# UART_CHANGER_INDICATION.net
KiCad netlist of a schematic drawn in Altium Designer
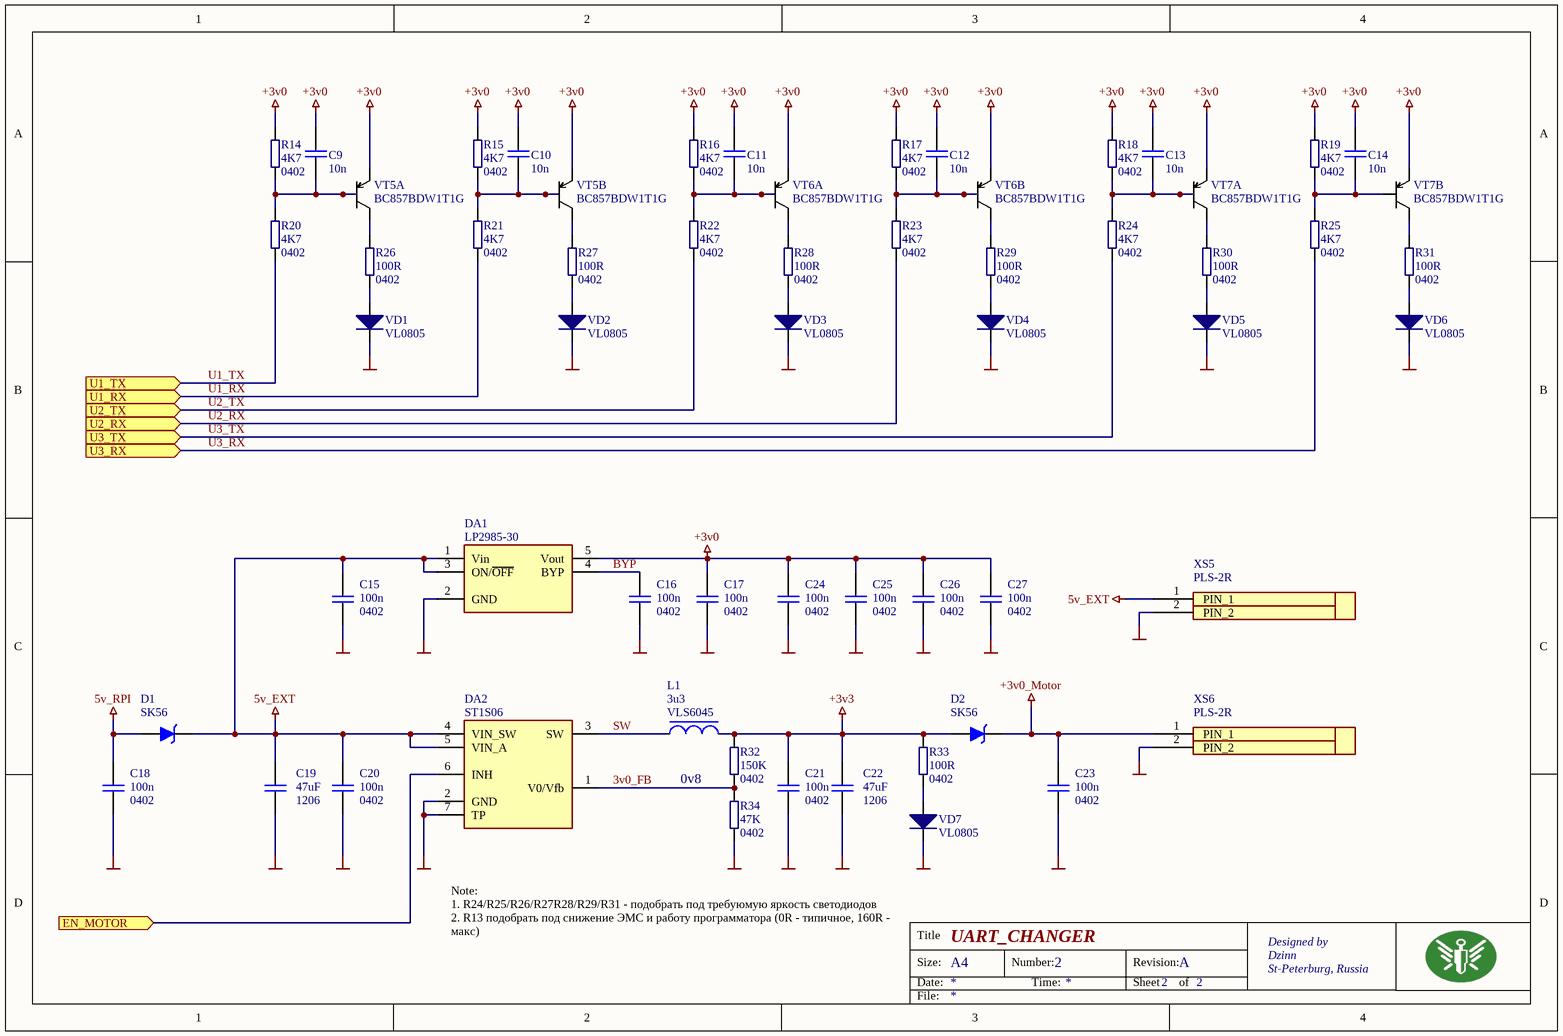
[diagram p0: UART_CHANGER_INDICATION.SchDoc]

(export (version "E")
  (design (tool "Eeschema 10.0.6"))
  (components
    (comp (ref "C9")
      (value "10n")
      (footprint "0402")
      (description "CAP 0402 100n")
      (fields
        (field (name "PART NUMBER") "C000001")
        (field (name "MANUFACTURER") "Murata")
        (field (name "CHECK FOOTPRINT") "A")
        (field (name "CHECK SYMBOL") "A")
      )
      (libsource (lib "Dzinn_lib") (part "CAP_NP"))
    )
    (comp (ref "C10")
      (value "10n")
      (footprint "0402")
      (description "CAP 0402 100n")
      (fields
        (field (name "PART NUMBER") "C000001")
        (field (name "MANUFACTURER") "Murata")
        (field (name "CHECK FOOTPRINT") "A")
        (field (name "CHECK SYMBOL") "A")
      )
      (libsource (lib "Dzinn_lib") (part "CAP_NP"))
    )
    (comp (ref "C11")
      (value "10n")
      (footprint "0402")
      (description "CAP 0402 100n")
      (fields
        (field (name "PART NUMBER") "C000001")
        (field (name "MANUFACTURER") "Murata")
        (field (name "CHECK FOOTPRINT") "A")
        (field (name "CHECK SYMBOL") "A")
      )
      (libsource (lib "Dzinn_lib") (part "CAP_NP"))
    )
    (comp (ref "C12")
      (value "10n")
      (footprint "0402")
      (description "CAP 0402 100n")
      (fields
        (field (name "PART NUMBER") "C000001")
        (field (name "MANUFACTURER") "Murata")
        (field (name "CHECK FOOTPRINT") "A")
        (field (name "CHECK SYMBOL") "A")
      )
      (libsource (lib "Dzinn_lib") (part "CAP_NP"))
    )
    (comp (ref "C13")
      (value "10n")
      (footprint "0402")
      (description "CAP 0402 100n")
      (fields
        (field (name "PART NUMBER") "C000001")
        (field (name "MANUFACTURER") "Murata")
        (field (name "CHECK FOOTPRINT") "A")
        (field (name "CHECK SYMBOL") "A")
      )
      (libsource (lib "Dzinn_lib") (part "CAP_NP"))
    )
    (comp (ref "C14")
      (value "10n")
      (footprint "0402")
      (description "CAP 0402 100n")
      (fields
        (field (name "PART NUMBER") "C000001")
        (field (name "MANUFACTURER") "Murata")
        (field (name "CHECK FOOTPRINT") "A")
        (field (name "CHECK SYMBOL") "A")
      )
      (libsource (lib "Dzinn_lib") (part "CAP_NP"))
    )
    (comp (ref "C15")
      (value "100n")
      (footprint "0402")
      (description "CAP 0402 100n")
      (fields
        (field (name "PART NUMBER") "C000001")
        (field (name "MANUFACTURER") "Murata")
        (field (name "PACKAGE") "0402")
        (field (name "CHECK FOOTPRINT") "A")
        (field (name "CHECK SYMBOL") "A")
      )
      (libsource (lib "Dzinn_lib") (part "CAP_NP"))
    )
    (comp (ref "C16")
      (value "100n")
      (footprint "0402")
      (description "CAP 0402 100n")
      (fields
        (field (name "PART NUMBER") "C000001")
        (field (name "MANUFACTURER") "Murata")
        (field (name "PACKAGE") "0402")
        (field (name "CHECK FOOTPRINT") "A")
        (field (name "CHECK SYMBOL") "A")
      )
      (libsource (lib "Dzinn_lib") (part "CAP_NP"))
    )
    (comp (ref "C17")
      (value "100n")
      (footprint "0402")
      (description "CAP 0402 100n")
      (fields
        (field (name "PART NUMBER") "C000001")
        (field (name "MANUFACTURER") "Murata")
        (field (name "PACKAGE") "0402")
        (field (name "CHECK FOOTPRINT") "A")
        (field (name "CHECK SYMBOL") "A")
      )
      (libsource (lib "Dzinn_lib") (part "CAP_NP"))
    )
    (comp (ref "C18")
      (value "100n")
      (footprint "0402")
      (description "CAP 0402 100n")
      (fields
        (field (name "PART NUMBER") "C000001")
        (field (name "MANUFACTURER") "Murata")
        (field (name "PACKAGE") "0402")
        (field (name "CHECK FOOTPRINT") "A")
        (field (name "CHECK SYMBOL") "A")
      )
      (libsource (lib "Dzinn_lib") (part "CAP_NP"))
    )
    (comp (ref "C19")
      (value "47uF")
      (footprint "1206")
      (description "CAP 1206 47uF 10V")
      (fields
        (field (name "PACKAGE") "1206")
        (field (name "PART NUMBER") "C000003")
        (field (name "MANUFACTURER") "Murata")
        (field (name "CHECK FOOTPRINT") "A")
        (field (name "CHECK SYMBOL") "A")
      )
      (libsource (lib "") (part "CAP_NP_1"))
    )
    (comp (ref "C20")
      (value "100n")
      (footprint "0402")
      (description "CAP 0402 100n")
      (fields
        (field (name "PART NUMBER") "C000001")
        (field (name "MANUFACTURER") "Murata")
        (field (name "PACKAGE") "0402")
        (field (name "CHECK FOOTPRINT") "A")
        (field (name "CHECK SYMBOL") "A")
      )
      (libsource (lib "Dzinn_lib") (part "CAP_NP"))
    )
    (comp (ref "C21")
      (value "100n")
      (footprint "0402")
      (description "CAP 0402 100n")
      (fields
        (field (name "PART NUMBER") "C000001")
        (field (name "MANUFACTURER") "Murata")
        (field (name "PACKAGE") "0402")
        (field (name "CHECK FOOTPRINT") "A")
        (field (name "CHECK SYMBOL") "A")
      )
      (libsource (lib "Dzinn_lib") (part "CAP_NP"))
    )
    (comp (ref "C22")
      (value "47uF")
      (footprint "1206")
      (description "CAP 1206 47uF 10V")
      (fields
        (field (name "PACKAGE") "1206")
        (field (name "PART NUMBER") "C000003")
        (field (name "MANUFACTURER") "Murata")
        (field (name "CHECK FOOTPRINT") "A")
        (field (name "CHECK SYMBOL") "A")
      )
      (libsource (lib "") (part "CAP_NP_1"))
    )
    (comp (ref "C23")
      (value "100n")
      (footprint "0402")
      (description "CAP 0402 100n")
      (fields
        (field (name "PART NUMBER") "C000001")
        (field (name "MANUFACTURER") "Murata")
        (field (name "PACKAGE") "0402")
        (field (name "CHECK FOOTPRINT") "A")
        (field (name "CHECK SYMBOL") "A")
      )
      (libsource (lib "Dzinn_lib") (part "CAP_NP"))
    )
    (comp (ref "C24")
      (value "100n")
      (footprint "0402")
      (description "CAP 0402 100n")
      (fields
        (field (name "PART NUMBER") "C000001")
        (field (name "MANUFACTURER") "Murata")
        (field (name "PACKAGE") "0402")
        (field (name "CHECK FOOTPRINT") "A")
        (field (name "CHECK SYMBOL") "A")
      )
      (libsource (lib "Dzinn_lib") (part "CAP_NP"))
    )
    (comp (ref "C25")
      (value "100n")
      (footprint "0402")
      (description "CAP 0402 100n")
      (fields
        (field (name "PART NUMBER") "C000001")
        (field (name "MANUFACTURER") "Murata")
        (field (name "PACKAGE") "0402")
        (field (name "CHECK FOOTPRINT") "A")
        (field (name "CHECK SYMBOL") "A")
      )
      (libsource (lib "Dzinn_lib") (part "CAP_NP"))
    )
    (comp (ref "C26")
      (value "100n")
      (footprint "0402")
      (description "CAP 0402 100n")
      (fields
        (field (name "PART NUMBER") "C000001")
        (field (name "MANUFACTURER") "Murata")
        (field (name "PACKAGE") "0402")
        (field (name "CHECK FOOTPRINT") "A")
        (field (name "CHECK SYMBOL") "A")
      )
      (libsource (lib "Dzinn_lib") (part "CAP_NP"))
    )
    (comp (ref "C27")
      (value "100n")
      (footprint "0402")
      (description "CAP 0402 100n")
      (fields
        (field (name "PART NUMBER") "C000001")
        (field (name "MANUFACTURER") "Murata")
        (field (name "PACKAGE") "0402")
        (field (name "CHECK FOOTPRINT") "A")
        (field (name "CHECK SYMBOL") "A")
      )
      (libsource (lib "Dzinn_lib") (part "CAP_NP"))
    )
    (comp (ref "D1")
      (value "SK56")
      (footprint "SMB")
      (description "60V 5A Schottky Diode")
      (fields
        (field (name "PART NUMBER") "VD00002")
        (field (name "MANUFACTURER") "SMC")
        (field (name "CHECK FOOTPRINT") "A")
        (field (name "CHECK SYMBOL") "A")
      )
      (libsource (lib "Dzinn_lib") (part "DIODE Schottky"))
    )
    (comp (ref "D2")
      (value "SK56")
      (footprint "SMB")
      (description "60V 5A Schottky Diode")
      (fields
        (field (name "PART NUMBER") "VD00002")
        (field (name "MANUFACTURER") "SMC")
        (field (name "CHECK FOOTPRINT") "A")
        (field (name "CHECK SYMBOL") "A")
      )
      (libsource (lib "Dzinn_lib") (part "DIODE Schottky"))
    )
    (comp (ref "DA1")
      (value "LP2985-30")
      (footprint "SOT-23-5")
      (description "150-mA Low-noise Low-dropout Regulator With Shutdown")
      (fields
        (field (name "PART NUMBER") "U00007")
        (field (name "MANUFACTURER") "TI")
        (field (name "CHECK FOOTPRINT") "B")
        (field (name "CHECK SYMBOL") "B")
      )
      (libsource (lib "Dzinn_lib") (part "LP2985-XX"))
    )
    (comp (ref "DA2")
      (value "ST1S06")
      (footprint "DFN-6TP")
      (fields
        (field (name "PART NUMBER") "U00027")
        (field (name "MANUFACTURER") "ST")
        (field (name "CHECK FOOTPRINT") "A")
        (field (name "CHECK SYMBOL") "A")
      )
      (libsource (lib "Dzinn_lib") (part "ST1S06"))
    )
    (comp (ref "L1")
      (value "3u3")
      (footprint "VLS6045")
      (description "3u3H smd power induction")
      (fields
        (field (name "PART NUMBER") "IND000010")
        (field (name "MANUFACTURER") "TDK")
        (field (name "PACKAGE") "VLS6045")
        (field (name "CHECK FOOTPRINT") "A")
        (field (name "CHECK SYMBOL") "A")
      )
      (libsource (lib "Dzinn_lib") (part "IND"))
    )
    (comp (ref "R14")
      (value "4K7")
      (footprint "0402")
      (description "RES SMD")
      (fields
        (field (name "PART NUMBER") "R000090")
        (field (name "MANUFACTURER") "Rohm Semiconductor")
        (field (name "PACKAGE") "0402")
        (field (name "CHECK FOOTPRINT") "A")
        (field (name "CHECK SYMBOL") "A")
      )
      (libsource (lib "Dzinn_lib") (part "RES"))
    )
    (comp (ref "R15")
      (value "4K7")
      (footprint "0402")
      (description "RES SMD")
      (fields
        (field (name "PART NUMBER") "R000090")
        (field (name "MANUFACTURER") "Rohm Semiconductor")
        (field (name "PACKAGE") "0402")
        (field (name "CHECK FOOTPRINT") "A")
        (field (name "CHECK SYMBOL") "A")
      )
      (libsource (lib "Dzinn_lib") (part "RES"))
    )
    (comp (ref "R16")
      (value "4K7")
      (footprint "0402")
      (description "RES SMD")
      (fields
        (field (name "PART NUMBER") "R000090")
        (field (name "MANUFACTURER") "Rohm Semiconductor")
        (field (name "PACKAGE") "0402")
        (field (name "CHECK FOOTPRINT") "A")
        (field (name "CHECK SYMBOL") "A")
      )
      (libsource (lib "Dzinn_lib") (part "RES"))
    )
    (comp (ref "R17")
      (value "4K7")
      (footprint "0402")
      (description "RES SMD")
      (fields
        (field (name "PART NUMBER") "R000090")
        (field (name "MANUFACTURER") "Rohm Semiconductor")
        (field (name "PACKAGE") "0402")
        (field (name "CHECK FOOTPRINT") "A")
        (field (name "CHECK SYMBOL") "A")
      )
      (libsource (lib "Dzinn_lib") (part "RES"))
    )
    (comp (ref "R18")
      (value "4K7")
      (footprint "0402")
      (description "RES SMD")
      (fields
        (field (name "PART NUMBER") "R000090")
        (field (name "MANUFACTURER") "Rohm Semiconductor")
        (field (name "PACKAGE") "0402")
        (field (name "CHECK FOOTPRINT") "A")
        (field (name "CHECK SYMBOL") "A")
      )
      (libsource (lib "Dzinn_lib") (part "RES"))
    )
    (comp (ref "R19")
      (value "4K7")
      (footprint "0402")
      (description "RES SMD")
      (fields
        (field (name "PART NUMBER") "R000090")
        (field (name "MANUFACTURER") "Rohm Semiconductor")
        (field (name "PACKAGE") "0402")
        (field (name "CHECK FOOTPRINT") "A")
        (field (name "CHECK SYMBOL") "A")
      )
      (libsource (lib "Dzinn_lib") (part "RES"))
    )
    (comp (ref "R20")
      (value "4K7")
      (footprint "0402")
      (description "RES SMD")
      (fields
        (field (name "PART NUMBER") "R000090")
        (field (name "MANUFACTURER") "Rohm Semiconductor")
        (field (name "PACKAGE") "0402")
        (field (name "CHECK FOOTPRINT") "A")
        (field (name "CHECK SYMBOL") "A")
      )
      (libsource (lib "Dzinn_lib") (part "RES"))
    )
    (comp (ref "R21")
      (value "4K7")
      (footprint "0402")
      (description "RES SMD")
      (fields
        (field (name "PART NUMBER") "R000090")
        (field (name "MANUFACTURER") "Rohm Semiconductor")
        (field (name "PACKAGE") "0402")
        (field (name "CHECK FOOTPRINT") "A")
        (field (name "CHECK SYMBOL") "A")
      )
      (libsource (lib "Dzinn_lib") (part "RES"))
    )
    (comp (ref "R22")
      (value "4K7")
      (footprint "0402")
      (description "RES SMD")
      (fields
        (field (name "PART NUMBER") "R000090")
        (field (name "MANUFACTURER") "Rohm Semiconductor")
        (field (name "PACKAGE") "0402")
        (field (name "CHECK FOOTPRINT") "A")
        (field (name "CHECK SYMBOL") "A")
      )
      (libsource (lib "Dzinn_lib") (part "RES"))
    )
    (comp (ref "R23")
      (value "4K7")
      (footprint "0402")
      (description "RES SMD")
      (fields
        (field (name "PART NUMBER") "R000090")
        (field (name "MANUFACTURER") "Rohm Semiconductor")
        (field (name "PACKAGE") "0402")
        (field (name "CHECK FOOTPRINT") "A")
        (field (name "CHECK SYMBOL") "A")
      )
      (libsource (lib "Dzinn_lib") (part "RES"))
    )
    (comp (ref "R24")
      (value "4K7")
      (footprint "0402")
      (description "RES SMD")
      (fields
        (field (name "PART NUMBER") "R000090")
        (field (name "MANUFACTURER") "Rohm Semiconductor")
        (field (name "PACKAGE") "0402")
        (field (name "CHECK FOOTPRINT") "A")
        (field (name "CHECK SYMBOL") "A")
      )
      (libsource (lib "Dzinn_lib") (part "RES"))
    )
    (comp (ref "R25")
      (value "4K7")
      (footprint "0402")
      (description "RES SMD")
      (fields
        (field (name "PART NUMBER") "R000090")
        (field (name "MANUFACTURER") "Rohm Semiconductor")
        (field (name "PACKAGE") "0402")
        (field (name "CHECK FOOTPRINT") "A")
        (field (name "CHECK SYMBOL") "A")
      )
      (libsource (lib "Dzinn_lib") (part "RES"))
    )
    (comp (ref "R26")
      (value "100R")
      (footprint "0402")
      (description "RES SMD")
      (fields
        (field (name "PART NUMBER") "R000050")
        (field (name "MANUFACTURER") "Rohm Semiconductor")
        (field (name "PACKAGE") "0402")
        (field (name "CHECK FOOTPRINT") "A")
        (field (name "CHECK SYMBOL") "A")
      )
      (libsource (lib "Dzinn_lib") (part "RES"))
    )
    (comp (ref "R27")
      (value "100R")
      (footprint "0402")
      (description "RES SMD")
      (fields
        (field (name "PART NUMBER") "R000050")
        (field (name "MANUFACTURER") "Rohm Semiconductor")
        (field (name "PACKAGE") "0402")
        (field (name "CHECK FOOTPRINT") "A")
        (field (name "CHECK SYMBOL") "A")
      )
      (libsource (lib "Dzinn_lib") (part "RES"))
    )
    (comp (ref "R28")
      (value "100R")
      (footprint "0402")
      (description "RES SMD")
      (fields
        (field (name "PART NUMBER") "R000050")
        (field (name "MANUFACTURER") "Rohm Semiconductor")
        (field (name "PACKAGE") "0402")
        (field (name "CHECK FOOTPRINT") "A")
        (field (name "CHECK SYMBOL") "A")
      )
      (libsource (lib "Dzinn_lib") (part "RES"))
    )
    (comp (ref "R29")
      (value "100R")
      (footprint "0402")
      (description "RES SMD")
      (fields
        (field (name "PART NUMBER") "R000050")
        (field (name "MANUFACTURER") "Rohm Semiconductor")
        (field (name "PACKAGE") "0402")
        (field (name "CHECK FOOTPRINT") "A")
        (field (name "CHECK SYMBOL") "A")
      )
      (libsource (lib "Dzinn_lib") (part "RES"))
    )
    (comp (ref "R30")
      (value "100R")
      (footprint "0402")
      (description "RES SMD")
      (fields
        (field (name "PART NUMBER") "R000050")
        (field (name "MANUFACTURER") "Rohm Semiconductor")
        (field (name "PACKAGE") "0402")
        (field (name "CHECK FOOTPRINT") "A")
        (field (name "CHECK SYMBOL") "A")
      )
      (libsource (lib "Dzinn_lib") (part "RES"))
    )
    (comp (ref "R31")
      (value "100R")
      (footprint "0402")
      (description "RES SMD")
      (fields
        (field (name "PART NUMBER") "R000050")
        (field (name "MANUFACTURER") "Rohm Semiconductor")
        (field (name "PACKAGE") "0402")
        (field (name "CHECK FOOTPRINT") "A")
        (field (name "CHECK SYMBOL") "A")
      )
      (libsource (lib "Dzinn_lib") (part "RES"))
    )
    (comp (ref "R32")
      (value "150K")
      (footprint "0402")
      (description "RES SMD")
      (fields
        (field (name "PART NUMBER") "R000126")
        (field (name "MANUFACTURER") "Rohm Semiconductor")
        (field (name "PACKAGE") "0402")
        (field (name "CHECK FOOTPRINT") "A")
        (field (name "CHECK SYMBOL") "A")
      )
      (libsource (lib "Dzinn_lib") (part "RES"))
    )
    (comp (ref "R33")
      (value "100R")
      (footprint "0402")
      (description "RES SMD")
      (fields
        (field (name "PART NUMBER") "R000050")
        (field (name "MANUFACTURER") "Rohm Semiconductor")
        (field (name "PACKAGE") "0402")
        (field (name "CHECK FOOTPRINT") "A")
        (field (name "CHECK SYMBOL") "A")
      )
      (libsource (lib "Dzinn_lib") (part "RES"))
    )
    (comp (ref "R34")
      (value "47K")
      (footprint "0402")
      (description "RES SMD")
      (fields
        (field (name "PART NUMBER") "R000114")
        (field (name "MANUFACTURER") "Rohm Semiconductor")
        (field (name "PACKAGE") "0402")
        (field (name "CHECK FOOTPRINT") "A")
        (field (name "CHECK SYMBOL") "A")
      )
      (libsource (lib "Dzinn_lib") (part "RES"))
    )
    (comp (ref "VD1")
      (value "VL0805")
      (footprint "VL0805")
      (description "SMD LED 0805")
      (fields
        (field (name "PART NUMBER") "LED000002")
        (field (name "VOLTAGE") "3,2")
        (field (name "CHECK FOOTPRINT") "A")
        (field (name "CHECK SYMBOL") "A")
      )
      (libsource (lib "Dzinn_lib") (part "SMD_LED"))
    )
    (comp (ref "VD2")
      (value "VL0805")
      (footprint "VL0805")
      (description "SMD LED 0805")
      (fields
        (field (name "PART NUMBER") "LED000002")
        (field (name "VOLTAGE") "3,2")
        (field (name "CHECK FOOTPRINT") "A")
        (field (name "CHECK SYMBOL") "A")
      )
      (libsource (lib "Dzinn_lib") (part "SMD_LED"))
    )
    (comp (ref "VD3")
      (value "VL0805")
      (footprint "VL0805")
      (description "SMD LED 0805")
      (fields
        (field (name "PART NUMBER") "LED000002")
        (field (name "VOLTAGE") "3,2")
        (field (name "CHECK FOOTPRINT") "A")
        (field (name "CHECK SYMBOL") "A")
      )
      (libsource (lib "Dzinn_lib") (part "SMD_LED"))
    )
    (comp (ref "VD4")
      (value "VL0805")
      (footprint "VL0805")
      (description "SMD LED 0805")
      (fields
        (field (name "PART NUMBER") "LED000002")
        (field (name "VOLTAGE") "3,2")
        (field (name "CHECK FOOTPRINT") "A")
        (field (name "CHECK SYMBOL") "A")
      )
      (libsource (lib "Dzinn_lib") (part "SMD_LED"))
    )
    (comp (ref "VD5")
      (value "VL0805")
      (footprint "VL0805")
      (description "SMD LED 0805")
      (fields
        (field (name "PART NUMBER") "LED000002")
        (field (name "VOLTAGE") "3,2")
        (field (name "CHECK FOOTPRINT") "A")
        (field (name "CHECK SYMBOL") "A")
      )
      (libsource (lib "Dzinn_lib") (part "SMD_LED"))
    )
    (comp (ref "VD6")
      (value "VL0805")
      (footprint "VL0805")
      (description "SMD LED 0805")
      (fields
        (field (name "PART NUMBER") "LED000002")
        (field (name "VOLTAGE") "3,2")
        (field (name "CHECK FOOTPRINT") "A")
        (field (name "CHECK SYMBOL") "A")
      )
      (libsource (lib "Dzinn_lib") (part "SMD_LED"))
    )
    (comp (ref "VD7")
      (value "VL0805")
      (footprint "VL0805")
      (description "SMD LED 0805")
      (fields
        (field (name "PART NUMBER") "LED000002")
        (field (name "VOLTAGE") "3,2")
        (field (name "CHECK FOOTPRINT") "A")
        (field (name "CHECK SYMBOL") "A")
      )
      (libsource (lib "Dzinn_lib") (part "SMD_LED"))
    )
    (comp (ref "VT5")
      (value "BC857BDW1T1G")
      (footprint "SOT-363")
      (description "45V 100mA Dual PNP Transistor")
      (fields
        (field (name "PART NUMBER") "VT00009")
        (field (name "MANUFACTURER") "ON")
        (field (name "CHECK FOOTPRINT") "A")
        (field (name "CHECK SYMBOL") "A")
      )
      (libsource (lib "Dzinn_lib") (part "DUAL PNP"))
    )
    (comp (ref "VT6")
      (value "BC857BDW1T1G")
      (footprint "SOT-363")
      (description "45V 100mA Dual PNP Transistor")
      (fields
        (field (name "PART NUMBER") "VT00009")
        (field (name "MANUFACTURER") "ON")
        (field (name "CHECK FOOTPRINT") "A")
        (field (name "CHECK SYMBOL") "A")
      )
      (libsource (lib "Dzinn_lib") (part "DUAL PNP"))
    )
    (comp (ref "VT7")
      (value "BC857BDW1T1G")
      (footprint "SOT-363")
      (description "45V 100mA Dual PNP Transistor")
      (fields
        (field (name "PART NUMBER") "VT00009")
        (field (name "MANUFACTURER") "ON")
        (field (name "CHECK FOOTPRINT") "A")
        (field (name "CHECK SYMBOL") "A")
      )
      (libsource (lib "Dzinn_lib") (part "DUAL PNP"))
    )
    (comp (ref "XS5")
      (value "PLS-2R")
      (footprint "PLS-2R")
      (description "2 PIN PLS right angle")
      (fields
        (field (name "PART NUMBER") "XS00002")
        (field (name "MANUFACTURER") "TE")
        (field (name "CHECK FOOTPRINT") "A")
        (field (name "CHECK SYMBOL") "A")
      )
      (libsource (lib "Dzinn_lib") (part "2_PIN_CON"))
    )
    (comp (ref "XS6")
      (value "PLS-2R")
      (footprint "PLS-2R")
      (description "2 PIN PLS right angle")
      (fields
        (field (name "PART NUMBER") "XS00002")
        (field (name "MANUFACTURER") "TE")
        (field (name "CHECK FOOTPRINT") "A")
        (field (name "CHECK SYMBOL") "A")
      )
      (libsource (lib "Dzinn_lib") (part "2_PIN_CON"))
    )
  )
  (nets
    (net (code "1") (name "+3v0") (class "Default")
      (node (ref "C10") (pin "1") (pinfunction "1_1") (pintype "passive"))
      (node (ref "C11") (pin "1") (pinfunction "1_1") (pintype "passive"))
      (node (ref "C12") (pin "1") (pinfunction "1_1") (pintype "passive"))
      (node (ref "C13") (pin "1") (pinfunction "1_1") (pintype "passive"))
      (node (ref "C14") (pin "1") (pinfunction "1_1") (pintype "passive"))
      (node (ref "C17") (pin "1") (pinfunction "1_1") (pintype "passive"))
      (node (ref "C24") (pin "1") (pinfunction "1_1") (pintype "passive"))
      (node (ref "C25") (pin "1") (pinfunction "1_1") (pintype "passive"))
      (node (ref "C26") (pin "1") (pinfunction "1_1") (pintype "passive"))
      (node (ref "C27") (pin "1") (pinfunction "1_1") (pintype "passive"))
      (node (ref "C9") (pin "1") (pinfunction "1_1") (pintype "passive"))
      (node (ref "DA1") (pin "5") (pinfunction "Vout_5") (pintype "passive"))
      (node (ref "R14") (pin "2") (pinfunction "2_2") (pintype "passive"))
      (node (ref "R15") (pin "2") (pinfunction "2_2") (pintype "passive"))
      (node (ref "R16") (pin "2") (pinfunction "2_2") (pintype "passive"))
      (node (ref "R17") (pin "2") (pinfunction "2_2") (pintype "passive"))
      (node (ref "R18") (pin "2") (pinfunction "2_2") (pintype "passive"))
      (node (ref "R19") (pin "2") (pinfunction "2_2") (pintype "passive"))
      (node (ref "VT5") (pin "1") (pinfunction "1_1") (pintype "passive"))
      (node (ref "VT5") (pin "4") (pinfunction "4_4") (pintype "passive"))
      (node (ref "VT6") (pin "1") (pinfunction "1_1") (pintype "passive"))
      (node (ref "VT6") (pin "4") (pinfunction "4_4") (pintype "passive"))
      (node (ref "VT7") (pin "1") (pinfunction "1_1") (pintype "passive"))
      (node (ref "VT7") (pin "4") (pinfunction "4_4") (pintype "passive"))
    )
    (net (code "2") (name "+3v0_Motor") (class "Default")
      (node (ref "C23") (pin "1") (pinfunction "1_1") (pintype "passive"))
      (node (ref "D2") (pin "2") (pinfunction "2_2") (pintype "passive"))
      (node (ref "XS6") (pin "1") (pinfunction "PIN_1_1") (pintype "passive"))
    )
    (net (code "3") (name "+3v3") (class "Default")
      (node (ref "C21") (pin "1") (pinfunction "1_1") (pintype "passive"))
      (node (ref "C22") (pin "1") (pinfunction "1_1") (pintype "passive"))
      (node (ref "D2") (pin "1") (pinfunction "1_1") (pintype "passive"))
      (node (ref "L1") (pin "2") (pinfunction "2_2") (pintype "passive"))
      (node (ref "R32") (pin "2") (pinfunction "2_2") (pintype "passive"))
      (node (ref "R33") (pin "2") (pinfunction "2_2") (pintype "passive"))
    )
    (net (code "4") (name "/3v0_FB") (class "Default")
      (node (ref "DA2") (pin "1") (pinfunction "V0/Vfb_1") (pintype "passive"))
      (node (ref "R32") (pin "1") (pinfunction "1_1") (pintype "passive"))
      (node (ref "R34") (pin "2") (pinfunction "2_2") (pintype "passive"))
    )
    (net (code "5") (name "/BYP") (class "Default")
      (node (ref "C16") (pin "1") (pinfunction "1_1") (pintype "passive"))
      (node (ref "DA1") (pin "4") (pinfunction "BYP_4") (pintype "passive"))
    )
    (net (code "6") (name "/EN_MOTOR") (class "Default")
      (node (ref "DA2") (pin "6") (pinfunction "INH_6") (pintype "passive"))
    )
    (net (code "7") (name "/SW") (class "Default")
      (node (ref "DA2") (pin "3") (pinfunction "SW_3") (pintype "passive"))
      (node (ref "L1") (pin "1") (pinfunction "1_1") (pintype "passive"))
    )
    (net (code "8") (name "/U1_RX") (class "Default")
      (node (ref "R21") (pin "1") (pinfunction "1_1") (pintype "passive"))
    )
    (net (code "9") (name "/U1_TX") (class "Default")
      (node (ref "R20") (pin "1") (pinfunction "1_1") (pintype "passive"))
    )
    (net (code "10") (name "/U2_RX") (class "Default")
      (node (ref "R23") (pin "1") (pinfunction "1_1") (pintype "passive"))
    )
    (net (code "11") (name "/U2_TX") (class "Default")
      (node (ref "R22") (pin "1") (pinfunction "1_1") (pintype "passive"))
    )
    (net (code "12") (name "/U3_RX") (class "Default")
      (node (ref "R25") (pin "1") (pinfunction "1_1") (pintype "passive"))
    )
    (net (code "13") (name "/U3_TX") (class "Default")
      (node (ref "R24") (pin "1") (pinfunction "1_1") (pintype "passive"))
    )
    (net (code "14") (name "5v_EXT") (class "Default")
      (node (ref "C15") (pin "1") (pinfunction "1_1") (pintype "passive"))
      (node (ref "C19") (pin "1") (pinfunction "1_1") (pintype "passive"))
      (node (ref "C20") (pin "1") (pinfunction "1_1") (pintype "passive"))
      (node (ref "D1") (pin "2") (pinfunction "2_2") (pintype "passive"))
      (node (ref "DA1") (pin "1") (pinfunction "Vin_1") (pintype "passive"))
      (node (ref "DA1") (pin "3") (pinfunction "ON/~{OFF}_3") (pintype "passive"))
      (node (ref "DA2") (pin "4") (pinfunction "VIN_SW_4") (pintype "passive"))
      (node (ref "DA2") (pin "5") (pinfunction "VIN_A_5") (pintype "passive"))
      (node (ref "XS5") (pin "1") (pinfunction "PIN_1_1") (pintype "passive"))
    )
    (net (code "15") (name "5v_RPI") (class "Default")
      (node (ref "C18") (pin "1") (pinfunction "1_1") (pintype "passive"))
      (node (ref "D1") (pin "1") (pinfunction "1_1") (pintype "passive"))
    )
    (net (code "16") (name "GND") (class "Default")
      (node (ref "C15") (pin "2") (pinfunction "2_2") (pintype "passive"))
      (node (ref "C16") (pin "2") (pinfunction "2_2") (pintype "passive"))
      (node (ref "C17") (pin "2") (pinfunction "2_2") (pintype "passive"))
      (node (ref "C18") (pin "2") (pinfunction "2_2") (pintype "passive"))
      (node (ref "C19") (pin "2") (pinfunction "2_2") (pintype "passive"))
      (node (ref "C20") (pin "2") (pinfunction "2_2") (pintype "passive"))
      (node (ref "C21") (pin "2") (pinfunction "2_2") (pintype "passive"))
      (node (ref "C22") (pin "2") (pinfunction "2_2") (pintype "passive"))
      (node (ref "C23") (pin "2") (pinfunction "2_2") (pintype "passive"))
      (node (ref "C24") (pin "2") (pinfunction "2_2") (pintype "passive"))
      (node (ref "C25") (pin "2") (pinfunction "2_2") (pintype "passive"))
      (node (ref "C26") (pin "2") (pinfunction "2_2") (pintype "passive"))
      (node (ref "C27") (pin "2") (pinfunction "2_2") (pintype "passive"))
      (node (ref "DA1") (pin "2") (pinfunction "GND_2") (pintype "passive"))
      (node (ref "DA2") (pin "2") (pinfunction "GND_2") (pintype "passive"))
      (node (ref "DA2") (pin "7") (pinfunction "TP_7") (pintype "passive"))
      (node (ref "R34") (pin "1") (pinfunction "1_1") (pintype "passive"))
      (node (ref "VD1") (pin "2") (pinfunction "2_2") (pintype "passive"))
      (node (ref "VD2") (pin "2") (pinfunction "2_2") (pintype "passive"))
      (node (ref "VD3") (pin "2") (pinfunction "2_2") (pintype "passive"))
      (node (ref "VD4") (pin "2") (pinfunction "2_2") (pintype "passive"))
      (node (ref "VD5") (pin "2") (pinfunction "2_2") (pintype "passive"))
      (node (ref "VD6") (pin "2") (pinfunction "2_2") (pintype "passive"))
      (node (ref "VD7") (pin "2") (pinfunction "2_2") (pintype "passive"))
      (node (ref "XS5") (pin "2") (pinfunction "PIN_2_2") (pintype "passive"))
      (node (ref "XS6") (pin "2") (pinfunction "PIN_2_2") (pintype "passive"))
    )
    (net (code "17") (name "Net-(C9-Pad2)") (class "Default")
      (node (ref "C9") (pin "2") (pinfunction "2_2") (pintype "passive"))
      (node (ref "R14") (pin "1") (pinfunction "1_1") (pintype "passive"))
      (node (ref "R20") (pin "2") (pinfunction "2_2") (pintype "passive"))
      (node (ref "VT5") (pin "5") (pinfunction "5_5") (pintype "passive"))
    )
    (net (code "18") (name "Net-(C10-Pad2)") (class "Default")
      (node (ref "C10") (pin "2") (pinfunction "2_2") (pintype "passive"))
      (node (ref "R15") (pin "1") (pinfunction "1_1") (pintype "passive"))
      (node (ref "R21") (pin "2") (pinfunction "2_2") (pintype "passive"))
      (node (ref "VT5") (pin "2") (pinfunction "2_2") (pintype "passive"))
    )
    (net (code "19") (name "Net-(C11-Pad2)") (class "Default")
      (node (ref "C11") (pin "2") (pinfunction "2_2") (pintype "passive"))
      (node (ref "R16") (pin "1") (pinfunction "1_1") (pintype "passive"))
      (node (ref "R22") (pin "2") (pinfunction "2_2") (pintype "passive"))
      (node (ref "VT6") (pin "5") (pinfunction "5_5") (pintype "passive"))
    )
    (net (code "20") (name "Net-(C12-Pad2)") (class "Default")
      (node (ref "C12") (pin "2") (pinfunction "2_2") (pintype "passive"))
      (node (ref "R17") (pin "1") (pinfunction "1_1") (pintype "passive"))
      (node (ref "R23") (pin "2") (pinfunction "2_2") (pintype "passive"))
      (node (ref "VT6") (pin "2") (pinfunction "2_2") (pintype "passive"))
    )
    (net (code "21") (name "Net-(C13-Pad2)") (class "Default")
      (node (ref "C13") (pin "2") (pinfunction "2_2") (pintype "passive"))
      (node (ref "R18") (pin "1") (pinfunction "1_1") (pintype "passive"))
      (node (ref "R24") (pin "2") (pinfunction "2_2") (pintype "passive"))
      (node (ref "VT7") (pin "5") (pinfunction "5_5") (pintype "passive"))
    )
    (net (code "22") (name "Net-(C14-Pad2)") (class "Default")
      (node (ref "C14") (pin "2") (pinfunction "2_2") (pintype "passive"))
      (node (ref "R19") (pin "1") (pinfunction "1_1") (pintype "passive"))
      (node (ref "R25") (pin "2") (pinfunction "2_2") (pintype "passive"))
      (node (ref "VT7") (pin "2") (pinfunction "2_2") (pintype "passive"))
    )
    (net (code "23") (name "Net-(R26-Pad1)") (class "Default")
      (node (ref "R26") (pin "1") (pinfunction "1_1") (pintype "passive"))
      (node (ref "VD1") (pin "1") (pinfunction "1_1") (pintype "passive"))
    )
    (net (code "24") (name "Net-(R26-Pad2)") (class "Default")
      (node (ref "R26") (pin "2") (pinfunction "2_2") (pintype "passive"))
      (node (ref "VT5") (pin "3") (pinfunction "3_3") (pintype "passive"))
    )
    (net (code "25") (name "Net-(R27-Pad1)") (class "Default")
      (node (ref "R27") (pin "1") (pinfunction "1_1") (pintype "passive"))
      (node (ref "VD2") (pin "1") (pinfunction "1_1") (pintype "passive"))
    )
    (net (code "26") (name "Net-(R27-Pad2)") (class "Default")
      (node (ref "R27") (pin "2") (pinfunction "2_2") (pintype "passive"))
      (node (ref "VT5") (pin "6") (pinfunction "6_6") (pintype "passive"))
    )
    (net (code "27") (name "Net-(R28-Pad1)") (class "Default")
      (node (ref "R28") (pin "1") (pinfunction "1_1") (pintype "passive"))
      (node (ref "VD3") (pin "1") (pinfunction "1_1") (pintype "passive"))
    )
    (net (code "28") (name "Net-(R28-Pad2)") (class "Default")
      (node (ref "R28") (pin "2") (pinfunction "2_2") (pintype "passive"))
      (node (ref "VT6") (pin "3") (pinfunction "3_3") (pintype "passive"))
    )
    (net (code "29") (name "Net-(R29-Pad1)") (class "Default")
      (node (ref "R29") (pin "1") (pinfunction "1_1") (pintype "passive"))
      (node (ref "VD4") (pin "1") (pinfunction "1_1") (pintype "passive"))
    )
    (net (code "30") (name "Net-(R29-Pad2)") (class "Default")
      (node (ref "R29") (pin "2") (pinfunction "2_2") (pintype "passive"))
      (node (ref "VT6") (pin "6") (pinfunction "6_6") (pintype "passive"))
    )
    (net (code "31") (name "Net-(R30-Pad1)") (class "Default")
      (node (ref "R30") (pin "1") (pinfunction "1_1") (pintype "passive"))
      (node (ref "VD5") (pin "1") (pinfunction "1_1") (pintype "passive"))
    )
    (net (code "32") (name "Net-(R30-Pad2)") (class "Default")
      (node (ref "R30") (pin "2") (pinfunction "2_2") (pintype "passive"))
      (node (ref "VT7") (pin "3") (pinfunction "3_3") (pintype "passive"))
    )
    (net (code "33") (name "Net-(R31-Pad1)") (class "Default")
      (node (ref "R31") (pin "1") (pinfunction "1_1") (pintype "passive"))
      (node (ref "VD6") (pin "1") (pinfunction "1_1") (pintype "passive"))
    )
    (net (code "34") (name "Net-(R31-Pad2)") (class "Default")
      (node (ref "R31") (pin "2") (pinfunction "2_2") (pintype "passive"))
      (node (ref "VT7") (pin "6") (pinfunction "6_6") (pintype "passive"))
    )
    (net (code "35") (name "Net-(R33-Pad1)") (class "Default")
      (node (ref "R33") (pin "1") (pinfunction "1_1") (pintype "passive"))
      (node (ref "VD7") (pin "1") (pinfunction "1_1") (pintype "passive"))
    )
  )
)
